# MainBoard.net
KiCad netlist of a schematic drawn in Altium Designer
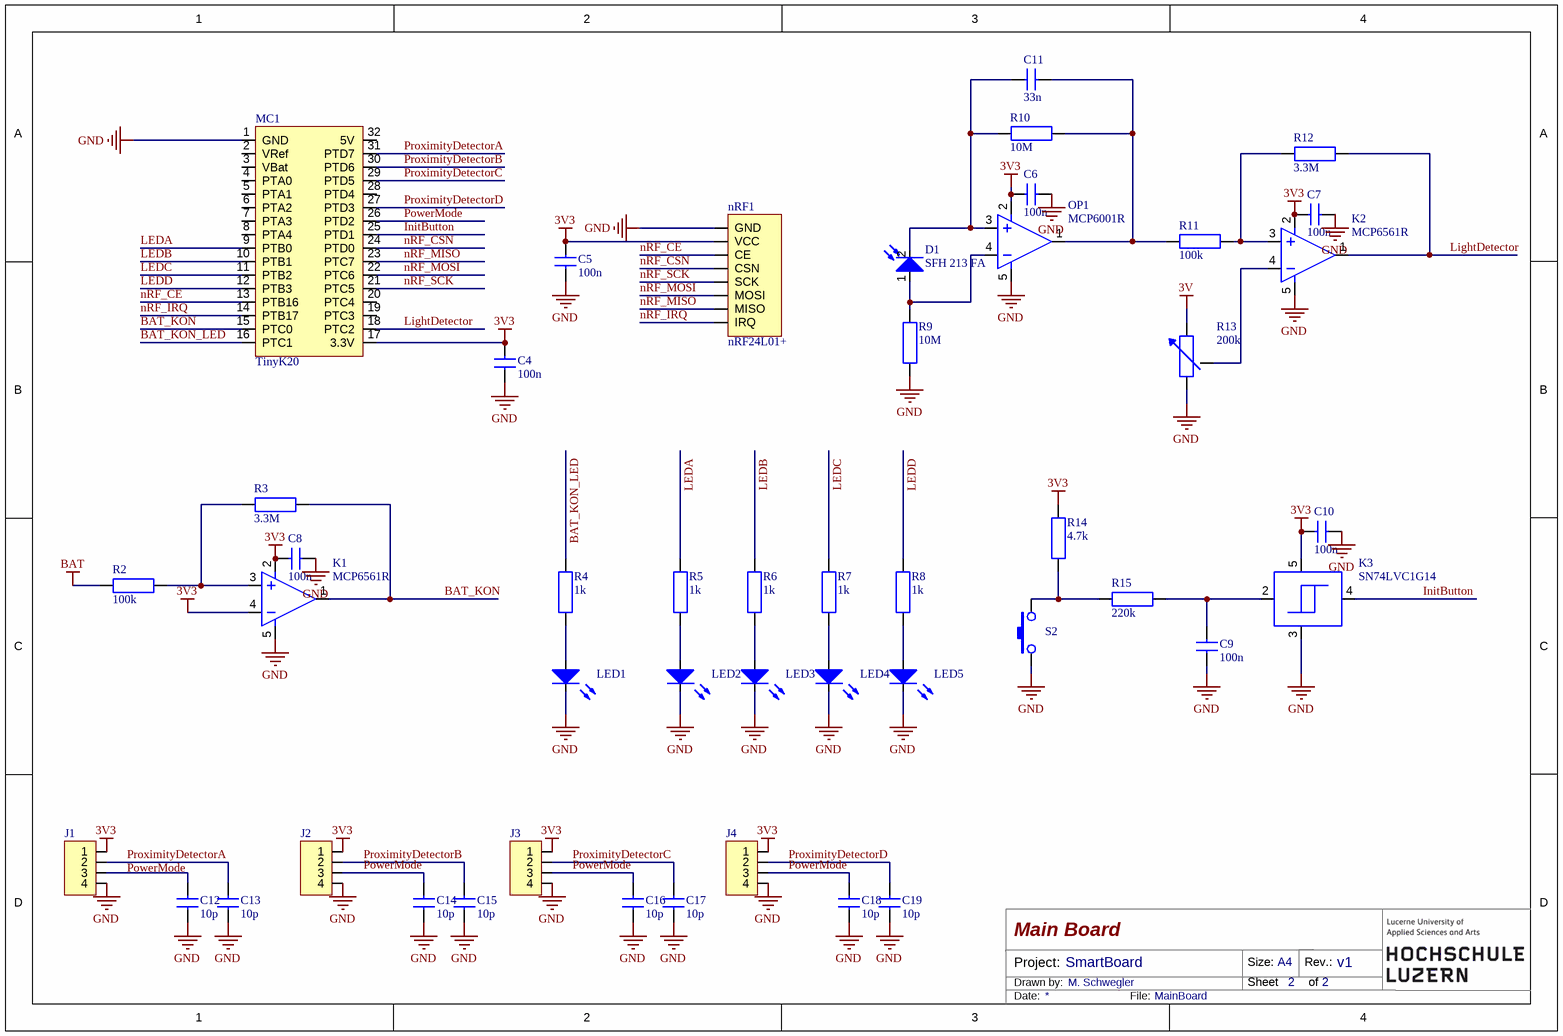
[diagram p0: MainBoard.SchDoc]

(export (version "E")
  (design (tool "Eeschema 10.0.6"))
  (components
    (comp (ref "C4")
      (value "100n")
      (footprint "0805_C")
      (description "Normaler Kondensator")
      (libsource (lib "MainBoard") (part "C?"))
    )
    (comp (ref "C5")
      (value "100n")
      (footprint "0805_C")
      (description "Normaler Kondensator")
      (libsource (lib "MainBoard") (part "C?"))
    )
    (comp (ref "C6")
      (value "100n")
      (footprint "0805_C")
      (description "Normaler Kondensator")
      (libsource (lib "MainBoard") (part "C?"))
    )
    (comp (ref "C7")
      (value "100n")
      (footprint "0805_C")
      (description "Normaler Kondensator")
      (libsource (lib "MainBoard") (part "C?"))
    )
    (comp (ref "C8")
      (value "100n")
      (footprint "0805_C")
      (description "Normaler Kondensator")
      (libsource (lib "MainBoard") (part "C?"))
    )
    (comp (ref "C9")
      (value "100n")
      (footprint "0805_C")
      (description "Normaler Kondensator")
      (libsource (lib "MainBoard") (part "C?"))
    )
    (comp (ref "C10")
      (value "100n")
      (footprint "0805_C")
      (description "Normaler Kondensator")
      (libsource (lib "MainBoard") (part "C?"))
    )
    (comp (ref "C11")
      (value "33n")
      (footprint "0805_C")
      (description "Normaler Kondensator")
      (libsource (lib "MainBoard") (part "C?"))
    )
    (comp (ref "C12")
      (value "10p")
      (footprint "0805_C")
      (description "Normaler Kondensator")
      (libsource (lib "MainBoard") (part "C?"))
    )
    (comp (ref "C13")
      (value "10p")
      (footprint "0805_C")
      (description "Normaler Kondensator")
      (libsource (lib "MainBoard") (part "C?"))
    )
    (comp (ref "C14")
      (value "10p")
      (footprint "0805_C")
      (description "Normaler Kondensator")
      (libsource (lib "MainBoard") (part "C?"))
    )
    (comp (ref "C15")
      (value "10p")
      (footprint "0805_C")
      (description "Normaler Kondensator")
      (libsource (lib "MainBoard") (part "C?"))
    )
    (comp (ref "C16")
      (value "10p")
      (footprint "0805_C")
      (description "Normaler Kondensator")
      (libsource (lib "MainBoard") (part "C?"))
    )
    (comp (ref "C17")
      (value "10p")
      (footprint "0805_C")
      (description "Normaler Kondensator")
      (libsource (lib "MainBoard") (part "C?"))
    )
    (comp (ref "C18")
      (value "10p")
      (footprint "0805_C")
      (description "Normaler Kondensator")
      (libsource (lib "MainBoard") (part "C?"))
    )
    (comp (ref "C19")
      (value "10p")
      (footprint "0805_C")
      (description "Normaler Kondensator")
      (libsource (lib "MainBoard") (part "C?"))
    )
    (comp (ref "D1")
      (value "SFH 213 FA")
      (footprint "LED_THT_5mm_RM_2.54mm")
      (description "Photo_Diode_1A_2K")
      (libsource (lib "Sch_Lib") (part "Photo_Diode_1A_2K"))
    )
    (comp (ref "J1") (value "~") (footprint "CON_THT_4P_RM2.54") (libsource (lib "Sch_Lib") (part "CON_4P")))
    (comp (ref "J2") (value "~") (footprint "CON_THT_4P_RM2.54") (libsource (lib "Sch_Lib") (part "CON_4P")))
    (comp (ref "J3") (value "~") (footprint "CON_THT_4P_RM2.54") (libsource (lib "Sch_Lib") (part "CON_4P")))
    (comp (ref "J4") (value "~") (footprint "CON_THT_4P_RM2.54") (libsource (lib "Sch_Lib") (part "CON_4P")))
    (comp (ref "K1") (value "MCP6561R") (footprint "SOT23-5") (libsource (lib "MainBoard") (part "OPAMP")))
    (comp (ref "K2") (value "MCP6561R") (footprint "SOT23-5") (libsource (lib "MainBoard") (part "OPAMP")))
    (comp (ref "K3")
      (value "SN74LVC1G14")
      (footprint "SOT23-5")
      (libsource (lib "MainBoard") (part "schmitt"))
    )
    (comp (ref "LED1")
      (value "~")
      (footprint "LED_THT_3mm_RM_2.54mm")
      (libsource (lib "Sch_Lib") (part "LED"))
    )
    (comp (ref "LED2")
      (value "~")
      (footprint "LED_THT_3mm_RM_2.54mm")
      (libsource (lib "Sch_Lib") (part "LED"))
    )
    (comp (ref "LED3")
      (value "~")
      (footprint "LED_THT_3mm_RM_2.54mm")
      (libsource (lib "Sch_Lib") (part "LED"))
    )
    (comp (ref "LED4")
      (value "~")
      (footprint "LED_THT_3mm_RM_2.54mm")
      (libsource (lib "Sch_Lib") (part "LED"))
    )
    (comp (ref "LED5")
      (value "~")
      (footprint "LED_THT_3mm_RM_2.54mm")
      (libsource (lib "Sch_Lib") (part "LED"))
    )
    (comp (ref "MC1") (value "TinyK20") (footprint "DIP32") (libsource (lib "MainBoard") (part "TinyK20")))
    (comp (ref "nRF1")
      (value "nRF24L01+")
      (footprint "CON_THT_2x4P_RM2.54_Stiftl")
      (libsource (lib "MainBoard") (part "Bluefruit"))
    )
    (comp (ref "OP1") (value "MCP6001R") (footprint "SOT23-5") (libsource (lib "MainBoard") (part "OPAMP")))
    (comp (ref "R2")
      (value "100k")
      (footprint "0805_R")
      (description "Normaler Widerstand")
      (libsource (lib "MainBoard") (part "R?"))
    )
    (comp (ref "R3")
      (value "3.3M")
      (footprint "0805_R")
      (description "Normaler Widerstand")
      (libsource (lib "MainBoard") (part "R?"))
    )
    (comp (ref "R4")
      (value "1k")
      (footprint "0805_R")
      (description "Normaler Widerstand")
      (libsource (lib "MainBoard") (part "R?"))
    )
    (comp (ref "R5")
      (value "1k")
      (footprint "0805_R")
      (description "Normaler Widerstand")
      (libsource (lib "MainBoard") (part "R?"))
    )
    (comp (ref "R6")
      (value "1k")
      (footprint "0805_R")
      (description "Normaler Widerstand")
      (libsource (lib "MainBoard") (part "R?"))
    )
    (comp (ref "R7")
      (value "1k")
      (footprint "0805_R")
      (description "Normaler Widerstand")
      (libsource (lib "MainBoard") (part "R?"))
    )
    (comp (ref "R8")
      (value "1k")
      (footprint "0805_R")
      (description "Normaler Widerstand")
      (libsource (lib "MainBoard") (part "R?"))
    )
    (comp (ref "R9")
      (value "10M")
      (footprint "0805_R")
      (description "Normaler Widerstand")
      (libsource (lib "MainBoard") (part "R?"))
    )
    (comp (ref "R10")
      (value "10M")
      (footprint "0805_R")
      (description "Normaler Widerstand")
      (libsource (lib "MainBoard") (part "R?"))
    )
    (comp (ref "R11")
      (value "100k")
      (footprint "0805_R")
      (description "Normaler Widerstand")
      (libsource (lib "MainBoard") (part "R?"))
    )
    (comp (ref "R12")
      (value "3.3M")
      (footprint "0805_R")
      (description "Normaler Widerstand")
      (libsource (lib "MainBoard") (part "R?"))
    )
    (comp (ref "R13")
      (value "200k")
      (footprint "Poti")
      (description "Variabler Widerstand")
      (libsource (lib "ProximityDetector") (part "R? {RPAR}"))
    )
    (comp (ref "R14")
      (value "4.7k")
      (footprint "0805_R")
      (description "Normaler Widerstand")
      (libsource (lib "MainBoard") (part "R?"))
    )
    (comp (ref "R15")
      (value "220k")
      (footprint "0805_r")
      (description "Normaler Widerstand")
      (libsource (lib "MainBoard") (part "R?"))
    )
    (comp (ref "S2") (value "S2") (footprint "SIP2") (libsource (lib "DEVICE_HSLU") (part "SW-PB")))
  )
  (nets
    (net (code "1") (name "/BAT_KON") (class "Default")
      (node (ref "K1") (pin "1") (pinfunction "1_1") (pintype "passive"))
      (node (ref "MC1") (pin "15") (pinfunction "PTC0_15") (pintype "passive"))
      (node (ref "R3") (pin "1") (pintype "passive"))
    )
    (net (code "2") (name "/BAT_KON_LED") (class "Default")
      (node (ref "MC1") (pin "16") (pinfunction "PTC1_16") (pintype "passive"))
      (node (ref "R4") (pin "1") (pintype "passive"))
    )
    (net (code "3") (name "/InitButton") (class "Default")
      (node (ref "K3") (pin "4") (pinfunction "4_4") (pintype "passive"))
      (node (ref "MC1") (pin "25") (pinfunction "PTD1_25") (pintype "passive"))
    )
    (net (code "4") (name "/LEDA") (class "Default")
      (node (ref "MC1") (pin "9") (pinfunction "PTB0_9") (pintype "passive"))
      (node (ref "R5") (pin "1") (pintype "passive"))
    )
    (net (code "5") (name "/LEDB") (class "Default")
      (node (ref "MC1") (pin "10") (pinfunction "PTB1_10") (pintype "passive"))
      (node (ref "R6") (pin "1") (pintype "passive"))
    )
    (net (code "6") (name "/LEDC") (class "Default")
      (node (ref "MC1") (pin "11") (pinfunction "PTB2_11") (pintype "passive"))
      (node (ref "R7") (pin "1") (pintype "passive"))
    )
    (net (code "7") (name "/LEDD") (class "Default")
      (node (ref "MC1") (pin "12") (pinfunction "PTB3_12") (pintype "passive"))
      (node (ref "R8") (pin "1") (pintype "passive"))
    )
    (net (code "8") (name "/LightDetector") (class "Default")
      (node (ref "K2") (pin "1") (pinfunction "1_1") (pintype "passive"))
      (node (ref "MC1") (pin "18") (pinfunction "PTC2_18") (pintype "passive"))
      (node (ref "R12") (pin "1") (pintype "passive"))
    )
    (net (code "9") (name "/PowerMode") (class "Default")
      (node (ref "C14") (pin "2") (pinfunction "2_2") (pintype "passive"))
      (node (ref "C16") (pin "2") (pinfunction "2_2") (pintype "passive"))
      (node (ref "C18") (pin "2") (pinfunction "2_2") (pintype "passive"))
      (node (ref "J2") (pin "3") (pinfunction "3_3") (pintype "passive"))
      (node (ref "J3") (pin "3") (pinfunction "3_3") (pintype "passive"))
      (node (ref "J4") (pin "3") (pinfunction "3_3") (pintype "passive"))
      (node (ref "MC1") (pin "26") (pinfunction "PTD2_26") (pintype "passive"))
    )
    (net (code "10") (name "/ProximityDetectorA") (class "Default")
      (node (ref "C13") (pin "2") (pinfunction "2_2") (pintype "passive"))
      (node (ref "J1") (pin "2") (pinfunction "2_2") (pintype "passive"))
      (node (ref "MC1") (pin "31") (pinfunction "PTD7_31") (pintype "passive"))
    )
    (net (code "11") (name "/ProximityDetectorB") (class "Default")
      (node (ref "C15") (pin "2") (pinfunction "2_2") (pintype "passive"))
      (node (ref "J2") (pin "2") (pinfunction "2_2") (pintype "passive"))
      (node (ref "MC1") (pin "30") (pinfunction "PTD6_30") (pintype "passive"))
    )
    (net (code "12") (name "/ProximityDetectorC") (class "Default")
      (node (ref "C17") (pin "2") (pinfunction "2_2") (pintype "passive"))
      (node (ref "J3") (pin "2") (pinfunction "2_2") (pintype "passive"))
      (node (ref "MC1") (pin "29") (pinfunction "PTD5_29") (pintype "passive"))
    )
    (net (code "13") (name "/ProximityDetectorD") (class "Default")
      (node (ref "C19") (pin "2") (pinfunction "2_2") (pintype "passive"))
      (node (ref "J4") (pin "2") (pinfunction "2_2") (pintype "passive"))
      (node (ref "MC1") (pin "27") (pinfunction "PTD3_27") (pintype "passive"))
    )
    (net (code "14") (name "/nRF_CE") (class "Default")
      (node (ref "MC1") (pin "13") (pinfunction "PTB16_13") (pintype "passive"))
      (node (ref "nRF1") (pin "3") (pinfunction "CE_3") (pintype "passive"))
    )
    (net (code "15") (name "/nRF_CSN") (class "Default")
      (node (ref "MC1") (pin "24") (pinfunction "PTD0_24") (pintype "passive"))
      (node (ref "nRF1") (pin "4") (pinfunction "CSN_4") (pintype "passive"))
    )
    (net (code "16") (name "/nRF_IRQ") (class "Default")
      (node (ref "MC1") (pin "14") (pinfunction "PTB17_14") (pintype "passive"))
      (node (ref "nRF1") (pin "8") (pinfunction "IRQ_8") (pintype "passive"))
    )
    (net (code "17") (name "/nRF_MISO") (class "Default")
      (node (ref "MC1") (pin "23") (pinfunction "PTC7_23") (pintype "passive"))
      (node (ref "nRF1") (pin "7") (pinfunction "MISO_7") (pintype "passive"))
    )
    (net (code "18") (name "/nRF_MOSI") (class "Default")
      (node (ref "MC1") (pin "22") (pinfunction "PTC6_22") (pintype "passive"))
      (node (ref "nRF1") (pin "6") (pinfunction "MOSI_6") (pintype "passive"))
    )
    (net (code "19") (name "/nRF_SCK") (class "Default")
      (node (ref "MC1") (pin "21") (pinfunction "PTC5_21") (pintype "passive"))
      (node (ref "nRF1") (pin "5") (pinfunction "SCK_5") (pintype "passive"))
    )
    (net (code "20") (name "3V") (class "Default") (node (ref "R13") (pin "3") (pintype "passive")))
    (net (code "21") (name "3V3") (class "Default")
      (node (ref "C10") (pin "1") (pinfunction "1_1") (pintype "passive"))
      (node (ref "C4") (pin "2") (pinfunction "2_2") (pintype "passive"))
      (node (ref "C5") (pin "2") (pinfunction "2_2") (pintype "passive"))
      (node (ref "C6") (pin "1") (pinfunction "1_1") (pintype "passive"))
      (node (ref "C7") (pin "1") (pinfunction "1_1") (pintype "passive"))
      (node (ref "C8") (pin "1") (pinfunction "1_1") (pintype "passive"))
      (node (ref "J1") (pin "1") (pinfunction "1_1") (pintype "passive"))
      (node (ref "J2") (pin "1") (pinfunction "1_1") (pintype "passive"))
      (node (ref "J3") (pin "1") (pinfunction "1_1") (pintype "passive"))
      (node (ref "J4") (pin "1") (pinfunction "1_1") (pintype "passive"))
      (node (ref "K1") (pin "2") (pinfunction "2_2") (pintype "passive"))
      (node (ref "K1") (pin "4") (pinfunction "4_4") (pintype "passive"))
      (node (ref "K2") (pin "2") (pinfunction "2_2") (pintype "passive"))
      (node (ref "K3") (pin "5") (pinfunction "5_5") (pintype "passive"))
      (node (ref "MC1") (pin "17") (pinfunction "3.3V_17") (pintype "passive"))
      (node (ref "OP1") (pin "2") (pinfunction "2_2") (pintype "passive"))
      (node (ref "R14") (pin "1") (pintype "passive"))
      (node (ref "nRF1") (pin "2") (pinfunction "VCC_2") (pintype "passive"))
    )
    (net (code "22") (name "BAT") (class "Default") (node (ref "R2") (pin "2") (pintype "passive")))
    (net (code "23") (name "GND") (class "Default")
      (node (ref "C10") (pin "2") (pinfunction "2_2") (pintype "passive"))
      (node (ref "C12") (pin "1") (pinfunction "1_1") (pintype "passive"))
      (node (ref "C13") (pin "1") (pinfunction "1_1") (pintype "passive"))
      (node (ref "C14") (pin "1") (pinfunction "1_1") (pintype "passive"))
      (node (ref "C15") (pin "1") (pinfunction "1_1") (pintype "passive"))
      (node (ref "C16") (pin "1") (pinfunction "1_1") (pintype "passive"))
      (node (ref "C17") (pin "1") (pinfunction "1_1") (pintype "passive"))
      (node (ref "C18") (pin "1") (pinfunction "1_1") (pintype "passive"))
      (node (ref "C19") (pin "1") (pinfunction "1_1") (pintype "passive"))
      (node (ref "C4") (pin "1") (pinfunction "1_1") (pintype "passive"))
      (node (ref "C5") (pin "1") (pinfunction "1_1") (pintype "passive"))
      (node (ref "C6") (pin "2") (pinfunction "2_2") (pintype "passive"))
      (node (ref "C7") (pin "2") (pinfunction "2_2") (pintype "passive"))
      (node (ref "C8") (pin "2") (pinfunction "2_2") (pintype "passive"))
      (node (ref "C9") (pin "1") (pinfunction "1_1") (pintype "passive"))
      (node (ref "J1") (pin "4") (pinfunction "4_4") (pintype "passive"))
      (node (ref "J2") (pin "4") (pinfunction "4_4") (pintype "passive"))
      (node (ref "J3") (pin "4") (pinfunction "4_4") (pintype "passive"))
      (node (ref "J4") (pin "4") (pinfunction "4_4") (pintype "passive"))
      (node (ref "K1") (pin "5") (pinfunction "5_5") (pintype "passive"))
      (node (ref "K2") (pin "5") (pinfunction "5_5") (pintype "passive"))
      (node (ref "K3") (pin "3") (pinfunction "3_3") (pintype "passive"))
      (node (ref "LED1") (pin "2") (pinfunction "K_2") (pintype "passive"))
      (node (ref "LED2") (pin "2") (pinfunction "K_2") (pintype "passive"))
      (node (ref "LED3") (pin "2") (pinfunction "K_2") (pintype "passive"))
      (node (ref "LED4") (pin "2") (pinfunction "K_2") (pintype "passive"))
      (node (ref "LED5") (pin "2") (pinfunction "K_2") (pintype "passive"))
      (node (ref "MC1") (pin "1") (pinfunction "GND_1") (pintype "passive"))
      (node (ref "OP1") (pin "5") (pinfunction "5_5") (pintype "passive"))
      (node (ref "R13") (pin "1") (pintype "passive"))
      (node (ref "R9") (pin "2") (pintype "passive"))
      (node (ref "S2") (pin "1") (pintype "passive"))
      (node (ref "nRF1") (pin "1") (pinfunction "GND_1") (pintype "passive"))
    )
    (net (code "24") (name "Net-(C9-Pad2)") (class "Default")
      (node (ref "C9") (pin "2") (pinfunction "2_2") (pintype "passive"))
      (node (ref "K3") (pin "2") (pinfunction "2_2") (pintype "passive"))
      (node (ref "R15") (pin "2") (pintype "passive"))
    )
    (net (code "25") (name "Net-(C11-Pad2)") (class "Default")
      (node (ref "C11") (pin "2") (pinfunction "2_2") (pintype "passive"))
      (node (ref "OP1") (pin "1") (pinfunction "1_1") (pintype "passive"))
      (node (ref "R10") (pin "1") (pintype "passive"))
      (node (ref "R11") (pin "2") (pintype "passive"))
    )
    (net (code "26") (name "Net-(C12-Pad2)") (class "Default")
      (node (ref "C12") (pin "2") (pinfunction "2_2") (pintype "passive"))
      (node (ref "J1") (pin "3") (pinfunction "3_3") (pintype "passive"))
    )
    (net (code "27") (name "Net-(D1-A)") (class "Default")
      (node (ref "D1") (pin "1") (pinfunction "A_1") (pintype "passive"))
      (node (ref "OP1") (pin "4") (pinfunction "4_4") (pintype "passive"))
      (node (ref "R9") (pin "1") (pintype "passive"))
    )
    (net (code "28") (name "Net-(D1-K)") (class "Default")
      (node (ref "C11") (pin "1") (pinfunction "1_1") (pintype "passive"))
      (node (ref "D1") (pin "2") (pinfunction "K_2") (pintype "passive"))
      (node (ref "OP1") (pin "3") (pinfunction "3_3") (pintype "passive"))
      (node (ref "R10") (pin "2") (pintype "passive"))
    )
    (net (code "29") (name "Net-(K1-Pad3)") (class "Default")
      (node (ref "K1") (pin "3") (pinfunction "3_3") (pintype "passive"))
      (node (ref "R2") (pin "1") (pintype "passive"))
      (node (ref "R3") (pin "2") (pintype "passive"))
    )
    (net (code "30") (name "Net-(K2-Pad3)") (class "Default")
      (node (ref "K2") (pin "3") (pinfunction "3_3") (pintype "passive"))
      (node (ref "R11") (pin "1") (pintype "passive"))
      (node (ref "R12") (pin "2") (pintype "passive"))
    )
    (net (code "31") (name "Net-(K2-Pad4)") (class "Default")
      (node (ref "K2") (pin "4") (pinfunction "4_4") (pintype "passive"))
      (node (ref "R13") (pin "2") (pintype "passive"))
    )
    (net (code "32") (name "Net-(LED1-A)") (class "Default")
      (node (ref "LED1") (pin "1") (pinfunction "A_1") (pintype "passive"))
      (node (ref "R4") (pin "2") (pintype "passive"))
    )
    (net (code "33") (name "Net-(LED2-A)") (class "Default")
      (node (ref "LED2") (pin "1") (pinfunction "A_1") (pintype "passive"))
      (node (ref "R5") (pin "2") (pintype "passive"))
    )
    (net (code "34") (name "Net-(LED3-A)") (class "Default")
      (node (ref "LED3") (pin "1") (pinfunction "A_1") (pintype "passive"))
      (node (ref "R6") (pin "2") (pintype "passive"))
    )
    (net (code "35") (name "Net-(LED4-A)") (class "Default")
      (node (ref "LED4") (pin "1") (pinfunction "A_1") (pintype "passive"))
      (node (ref "R7") (pin "2") (pintype "passive"))
    )
    (net (code "36") (name "Net-(LED5-A)") (class "Default")
      (node (ref "LED5") (pin "1") (pinfunction "A_1") (pintype "passive"))
      (node (ref "R8") (pin "2") (pintype "passive"))
    )
    (net (code "37") (name "Net-(R14-Pad2)") (class "Default")
      (node (ref "R14") (pin "2") (pintype "passive"))
      (node (ref "R15") (pin "1") (pintype "passive"))
      (node (ref "S2") (pin "2") (pintype "passive"))
    )
    (net (code "38") (name "unconnected-(MC1-5V-Pad32)") (class "Default")
      (node (ref "MC1") (pin "32") (pinfunction "5V_32") (pintype "passive"))
    )
    (net (code "39") (name "unconnected-(MC1-PTA0-Pad4)") (class "Default")
      (node (ref "MC1") (pin "4") (pinfunction "PTA0_4") (pintype "passive"))
    )
    (net (code "40") (name "unconnected-(MC1-PTA1-Pad5)") (class "Default")
      (node (ref "MC1") (pin "5") (pinfunction "PTA1_5") (pintype "passive"))
    )
    (net (code "41") (name "unconnected-(MC1-PTA2-Pad6)") (class "Default")
      (node (ref "MC1") (pin "6") (pinfunction "PTA2_6") (pintype "passive"))
    )
    (net (code "42") (name "unconnected-(MC1-PTA3-Pad7)") (class "Default")
      (node (ref "MC1") (pin "7") (pinfunction "PTA3_7") (pintype "passive"))
    )
    (net (code "43") (name "unconnected-(MC1-PTA4-Pad8)") (class "Default")
      (node (ref "MC1") (pin "8") (pinfunction "PTA4_8") (pintype "passive"))
    )
    (net (code "44") (name "unconnected-(MC1-PTC3-Pad19)") (class "Default")
      (node (ref "MC1") (pin "19") (pinfunction "PTC3_19") (pintype "passive"))
    )
    (net (code "45") (name "unconnected-(MC1-PTC4-Pad20)") (class "Default")
      (node (ref "MC1") (pin "20") (pinfunction "PTC4_20") (pintype "passive"))
    )
    (net (code "46") (name "unconnected-(MC1-PTD4-Pad28)") (class "Default")
      (node (ref "MC1") (pin "28") (pinfunction "PTD4_28") (pintype "passive"))
    )
    (net (code "47") (name "unconnected-(MC1-VBat-Pad3)") (class "Default")
      (node (ref "MC1") (pin "3") (pinfunction "VBat_3") (pintype "passive"))
    )
    (net (code "48") (name "unconnected-(MC1-VRef-Pad2)") (class "Default")
      (node (ref "MC1") (pin "2") (pinfunction "VRef_2") (pintype "passive"))
    )
  )
)
